# yard-ice-power.net
KiCad netlist of a schematic drawn in Altium Designer
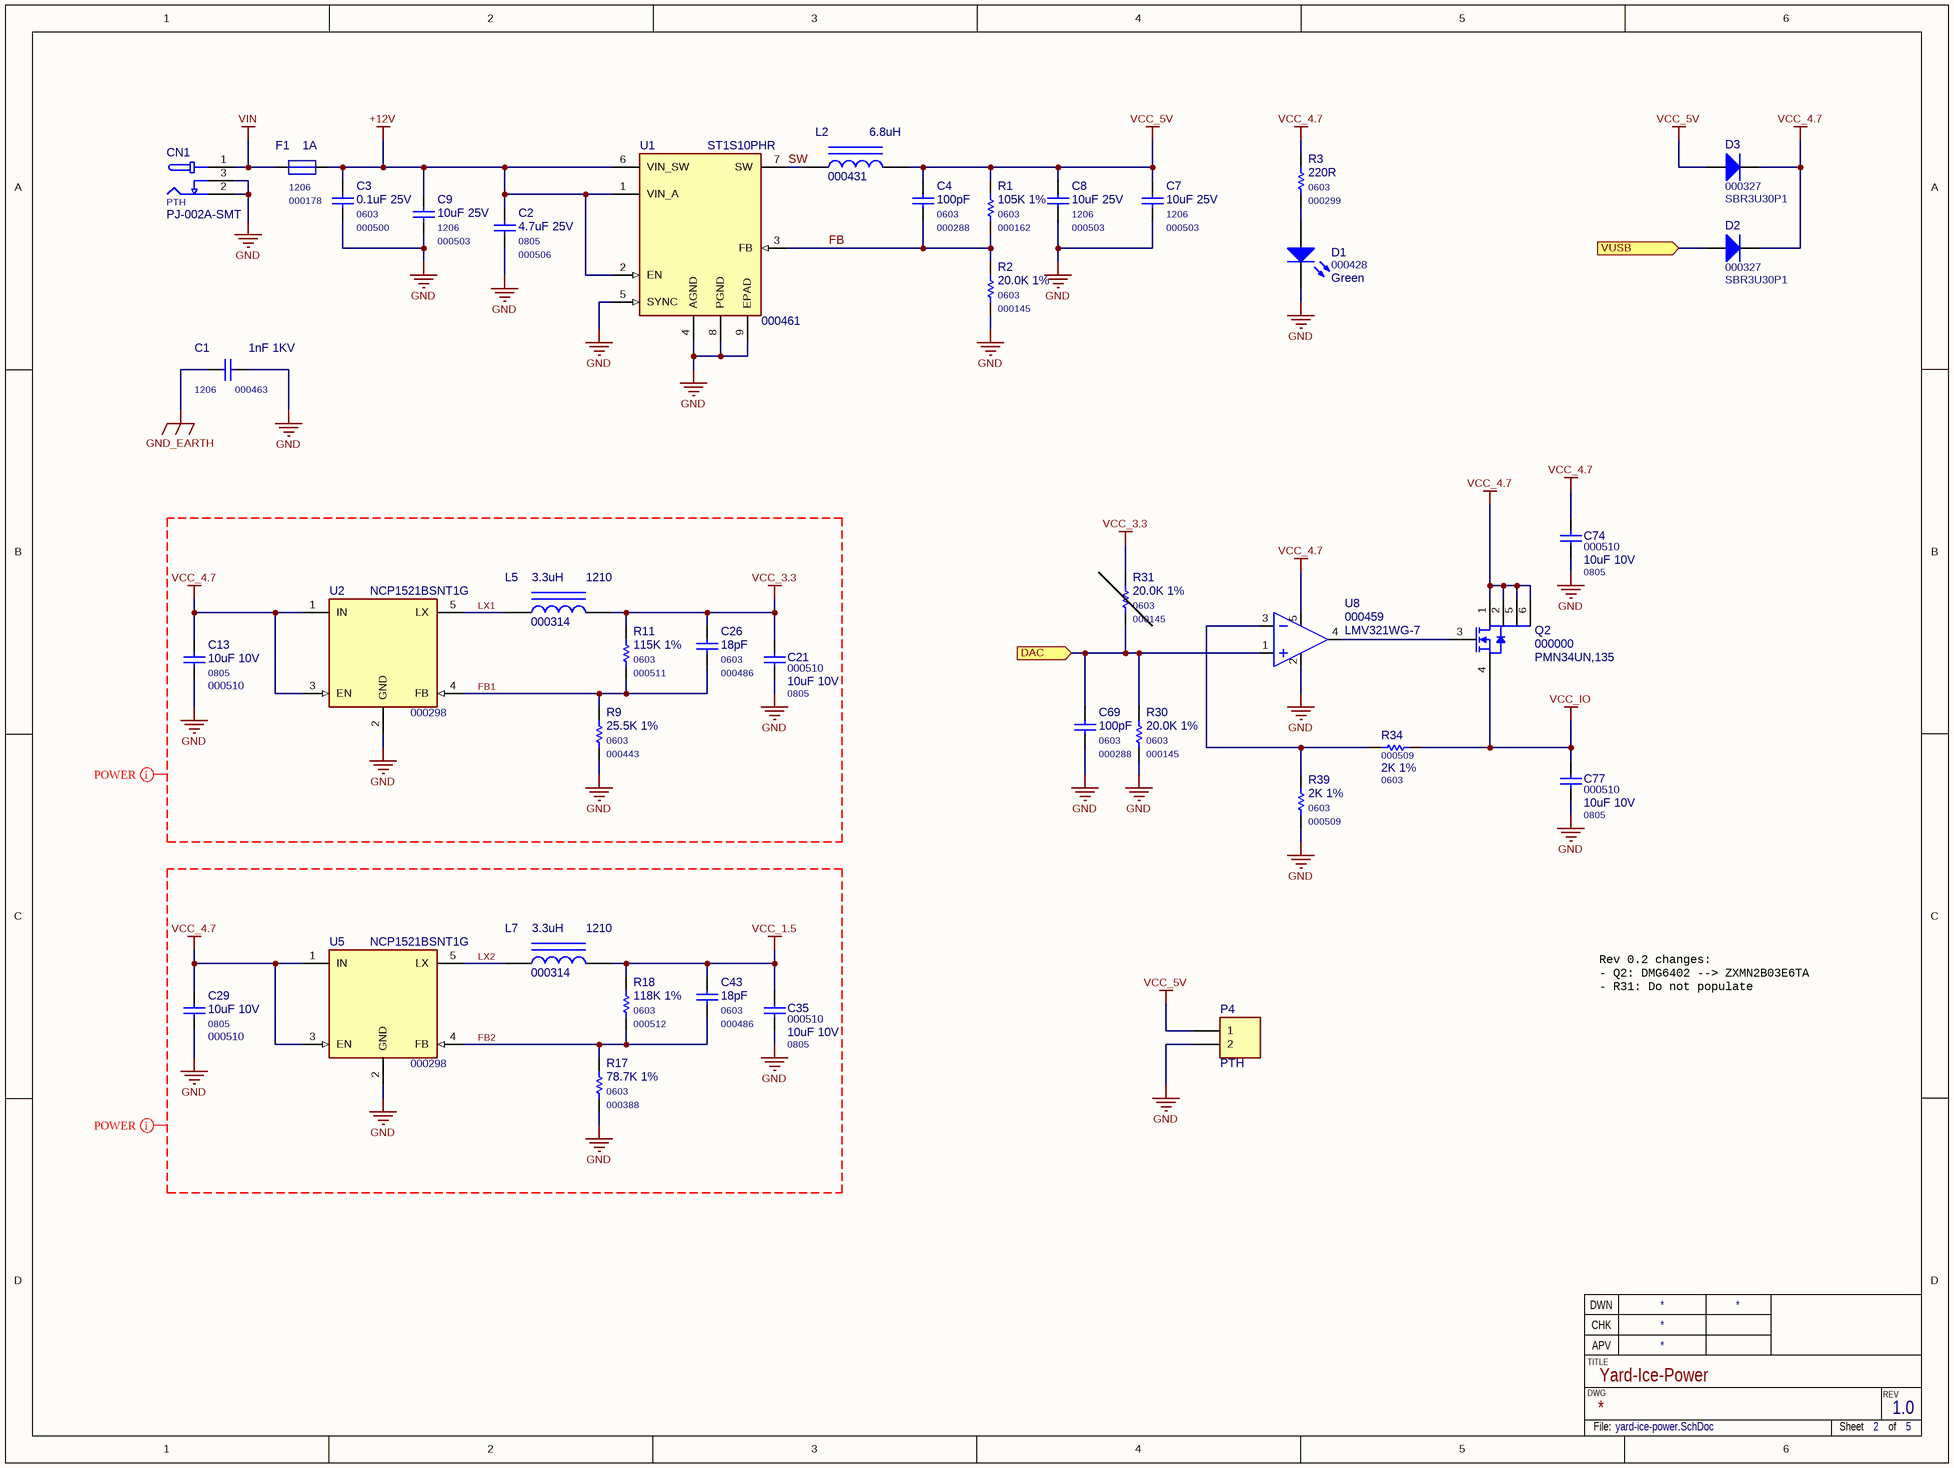
[diagram p0: yard-ice-power.SchDoc]

(export (version "E")
  (design (tool "Eeschema 10.0.6"))
  (components
    (comp (ref "C1")
      (value "000463")
      (footprint "C1206M")
      (description "SMD Ceramic Chip Capacitor - 1206")
      (fields (field (name "ALTIUM_VALUE") "1nF 1KV") (field (name "PACKAGE") "1206"))
      (libsource (lib "discrete-sm") (part "C1206"))
    )
    (comp (ref "C2")
      (value "000506")
      (footprint "C0805M")
      (description "SMD Ceramic Chip Capacitor - 0805 - X7R")
      (fields
        (field (name "ALTIUM_VALUE") "4.7uF 25V")
        (field (name "PACKAGE") "0805")
        (field (name "MF") "Taiyo Yuden")
      )
      (libsource (lib "discrete-sm") (part "C0805"))
    )
    (comp (ref "C3")
      (value "000500")
      (footprint "C0603M")
      (description "SMD Ceramic Chip Capacitor - 0603 - X7R")
      (fields
        (field (name "ALTIUM_VALUE") "0.1uF 25V")
        (field (name "PACKAGE") "0603")
        (field (name "MF") "TDK")
      )
      (libsource (lib "discrete-sm") (part "C0603"))
    )
    (comp (ref "C4")
      (value "000288")
      (footprint "C0603M")
      (description "SMD Ceramic Chip Capacitor - 0603")
      (fields (field (name "ALTIUM_VALUE") "100pF") (field (name "PACKAGE") "0603"))
      (libsource (lib "discrete-sm") (part "C0603"))
    )
    (comp (ref "C7")
      (value "000503")
      (footprint "C1206M")
      (description "SMD Ceramic Chip Capacitor - 1206 - X7R")
      (fields
        (field (name "ALTIUM_VALUE") "10uF 25V")
        (field (name "PACKAGE") "1206")
        (field (name "MF") "Taiyo Yuden")
      )
      (libsource (lib "discrete-sm") (part "C1206"))
    )
    (comp (ref "C8")
      (value "000503")
      (footprint "C1206M")
      (description "SMD Ceramic Chip Capacitor - 1206 - X7R")
      (fields
        (field (name "ALTIUM_VALUE") "10uF 25V")
        (field (name "PACKAGE") "1206")
        (field (name "MF") "Taiyo Yuden")
      )
      (libsource (lib "discrete-sm") (part "C1206"))
    )
    (comp (ref "C9")
      (value "000503")
      (footprint "C1206M")
      (description "SMD Ceramic Chip Capacitor - 1206 - X7R")
      (fields
        (field (name "ALTIUM_VALUE") "10uF 25V")
        (field (name "PACKAGE") "1206")
        (field (name "MF") "Taiyo Yuden")
      )
      (libsource (lib "discrete-sm") (part "C1206"))
    )
    (comp (ref "C13")
      (value "000510")
      (footprint "C0805M")
      (description "SMD Ceramic Chip Capacitor - 0805 - X7R")
      (fields
        (field (name "ALTIUM_VALUE") "10uF 10V")
        (field (name "PACKAGE") "0805")
        (field (name "MF") "TDK")
      )
      (libsource (lib "sm_cap") (part "C0805"))
    )
    (comp (ref "C21")
      (value "000510")
      (footprint "C0805M")
      (description "SMD Ceramic Chip Capacitor - 0805 - X7R")
      (fields
        (field (name "ALTIUM_VALUE") "10uF 10V")
        (field (name "PACKAGE") "0805")
        (field (name "MF") "TDK")
      )
      (libsource (lib "sm_cap") (part "C0805"))
    )
    (comp (ref "C26")
      (value "000486")
      (footprint "C0603M")
      (description "SMD Ceramic Chip Capacitor - 0603")
      (fields (field (name "ALTIUM_VALUE") "18pF") (field (name "PACKAGE") "0603"))
      (libsource (lib "discrete-sm") (part "C0603"))
    )
    (comp (ref "C29")
      (value "000510")
      (footprint "C0805M")
      (description "SMD Ceramic Chip Capacitor - 0805 - X7R")
      (fields
        (field (name "ALTIUM_VALUE") "10uF 10V")
        (field (name "PACKAGE") "0805")
        (field (name "MF") "TDK")
      )
      (libsource (lib "sm_cap") (part "C0805"))
    )
    (comp (ref "C35")
      (value "000510")
      (footprint "C0805M")
      (description "SMD Ceramic Chip Capacitor - 0805 - X7R")
      (fields
        (field (name "ALTIUM_VALUE") "10uF 10V")
        (field (name "PACKAGE") "0805")
        (field (name "MF") "TDK")
      )
      (libsource (lib "sm_cap") (part "C0805"))
    )
    (comp (ref "C43")
      (value "000486")
      (footprint "C0603M")
      (description "SMD Ceramic Chip Capacitor - 0603")
      (fields (field (name "ALTIUM_VALUE") "18pF") (field (name "PACKAGE") "0603"))
      (libsource (lib "discrete-sm") (part "C0603"))
    )
    (comp (ref "C69")
      (value "000288")
      (footprint "C0603M")
      (description "SMD Ceramic Chip Capacitor - 0603")
      (fields (field (name "ALTIUM_VALUE") "100pF") (field (name "PACKAGE") "0603"))
      (libsource (lib "discrete-sm") (part "C0603"))
    )
    (comp (ref "C74")
      (value "TDK")
      (footprint "C0805M")
      (description "SMD Ceramic Chip Capacitor - 0805 - X7R")
      (fields (field (name "ALTIUM_VALUE") "10uF 10V") (field (name "PACKAGE") "0805"))
      (libsource (lib "sm_cap") (part "C0805"))
    )
    (comp (ref "C77")
      (value "TDK")
      (footprint "C0805M")
      (description "SMD Ceramic Chip Capacitor - 0805 - X7R")
      (fields (field (name "ALTIUM_VALUE") "10uF 10V") (field (name "PACKAGE") "0805"))
      (libsource (lib "sm_cap") (part "C0805"))
    )
    (comp (ref "CN1")
      (value "PTH")
      (footprint "PJ-002A-SMT")
      (description "Low Voltage Power Supply Connector")
      (fields (field (name "MF") "CUI INC") (field (name "MF PN") "PJ-002A-SMT"))
      (libsource (lib "cui") (part "PJ-002A-SMT"))
    )
    (comp (ref "D1")
      (value "000428")
      (footprint "LED0805L LP")
      (description "LED SMD 0805")
      (fields (field (name "ALTIUM_VALUE") "Green"))
      (libsource (lib "discrete-sm") (part "LED0805LP"))
    )
    (comp (ref "D2")
      (value "000327")
      (footprint "PowerDI 123")
      (description "Super Barrier Rectifier")
      (fields (field (name "ALTIUM_VALUE") "SBR3U30P1") (field (name "MF") "Diodes Inc"))
      (libsource (lib "diodes-inc") (part "SBR3U30P1"))
    )
    (comp (ref "D3")
      (value "000327")
      (footprint "PowerDI 123")
      (description "Super Barrier Rectifier")
      (fields (field (name "ALTIUM_VALUE") "SBR3U30P1") (field (name "MF") "Diodes Inc"))
      (libsource (lib "diodes-inc") (part "SBR3U30P1"))
    )
    (comp (ref "F1")
      (value "000178")
      (footprint "F1206L")
      (description "SMD Fuse, 1A, Slow, 63VDC, 1206")
      (fields
        (field (name "ALTIUM_VALUE") "1A")
        (field (name "PACKAGE") "1206")
        (field (name "MF") "Bel Fuse Inc")
      )
      (libsource (lib "discrete-sm") (part "F1206"))
    )
    (comp (ref "L2")
      (value "000431")
      (footprint "L8.0MMX8.0MM")
      (description "SMT Power Inductor 8.0X8.0mm")
      (fields (field (name "ALTIUM_VALUE") "6.8uH") (field (name "MF") "Taiyo Yuden"))
      (libsource (lib "discrete-sm") (part "L8.0X8.0"))
    )
    (comp (ref "L5")
      (value "000314")
      (footprint "L1210M")
      (description "SMD Wire Wound Inductor -  1210 (3225 metric)")
      (fields
        (field (name "MF") "Murata")
        (field (name "PACKAGE") "1210")
        (field (name "ALTIUM_VALUE") "3.3uH")
      )
      (libsource (lib "discrete-sm") (part "L1210"))
    )
    (comp (ref "L7")
      (value "000314")
      (footprint "L1210M")
      (description "SMD Wire Wound Inductor -  1210 (3225 metric)")
      (fields
        (field (name "MF") "Murata")
        (field (name "PACKAGE") "1210")
        (field (name "ALTIUM_VALUE") "3.3uH")
      )
      (libsource (lib "discrete-sm") (part "L1210"))
    )
    (comp (ref "P4")
      (value "PTH")
      (footprint "TSW-102-07-G-S")
      (description "Header, 2-Pin")
      (libsource (lib "samtec-board-to-board") (part "Header 2"))
    )
    (comp (ref "Q2")
      (value "000000")
      (footprint "SOT-26")
      (description "N-Channel MOSFET 30V 4.9A 6TSOP")
      (fields (field (name "ALTIUM_VALUE") "PMN34UN,135"))
      (libsource (lib "nxp") (part "PMN34UN,135"))
    )
    (comp (ref "R1")
      (value "000162")
      (footprint "R0603M")
      (description "SMD Chip Resistor - 0603")
      (fields (field (name "ALTIUM_VALUE") "105K 1%") (field (name "PACKAGE") "0603"))
      (libsource (lib "discrete-sm") (part "R0603"))
    )
    (comp (ref "R2")
      (value "000145")
      (footprint "R0603M")
      (description "SMD Chip Resistor - 0603")
      (fields (field (name "ALTIUM_VALUE") "20.0K 1%") (field (name "PACKAGE") "0603"))
      (libsource (lib "discrete-sm") (part "R0603"))
    )
    (comp (ref "R3")
      (value "000299")
      (footprint "R0603M")
      (description "SMD Chip Resistor - 0603")
      (fields (field (name "ALTIUM_VALUE") "220R") (field (name "PACKAGE") "0603"))
      (libsource (lib "discrete-sm") (part "R0603"))
    )
    (comp (ref "R9")
      (value "000443")
      (footprint "R0603M")
      (description "SMD Chip Resistor - 0603")
      (fields (field (name "ALTIUM_VALUE") "25.5K 1%") (field (name "PACKAGE") "0603"))
      (libsource (lib "discrete-sm") (part "R0603"))
    )
    (comp (ref "R11")
      (value "000511")
      (footprint "R0603M")
      (description "SMD Chip Resistor - 0603")
      (fields (field (name "ALTIUM_VALUE") "115K 1%") (field (name "PACKAGE") "0603"))
      (libsource (lib "discrete-sm") (part "R0603"))
    )
    (comp (ref "R17")
      (value "000388")
      (footprint "R0603M")
      (description "SMD Chip Resistor - 0603")
      (fields (field (name "ALTIUM_VALUE") "78.7K 1%") (field (name "PACKAGE") "0603"))
      (libsource (lib "discrete-sm") (part "R0603"))
    )
    (comp (ref "R18")
      (value "000512")
      (footprint "R0603M")
      (description "SMD Chip Resistor - 0603")
      (fields (field (name "ALTIUM_VALUE") "118K 1%") (field (name "PACKAGE") "0603"))
      (libsource (lib "discrete-sm") (part "R0603"))
    )
    (comp (ref "R30")
      (value "000145")
      (footprint "R0603M")
      (description "SMD Chip Resistor - 0603")
      (fields (field (name "ALTIUM_VALUE") "20.0K 1%") (field (name "PACKAGE") "0603"))
      (libsource (lib "discrete-sm") (part "R0603"))
    )
    (comp (ref "R31")
      (value "000145")
      (footprint "R0603M")
      (description "SMD Chip Resistor - 0603")
      (fields (field (name "ALTIUM_VALUE") "20.0K 1%") (field (name "PACKAGE") "0603"))
      (libsource (lib "discrete-sm") (part "R0603"))
    )
    (comp (ref "R34")
      (value "000509")
      (footprint "R0603M")
      (description "SMD Chip Resistor - 0603")
      (fields (field (name "ALTIUM_VALUE") "2K 1%") (field (name "PACKAGE") "0603"))
      (libsource (lib "discrete-sm") (part "R0603"))
    )
    (comp (ref "R39")
      (value "000509")
      (footprint "R0603M")
      (description "SMD Chip Resistor - 0603")
      (fields (field (name "ALTIUM_VALUE") "2K 1%") (field (name "PACKAGE") "0603"))
      (libsource (lib "discrete-sm") (part "R0603"))
    )
    (comp (ref "U1")
      (value "000461")
      (footprint "PowerSO-8")
      (description "3A, 900kHZ, monolithic synchronous step-down regulator")
      (fields (field (name "ALTIUM_VALUE") "ST1S10PHR") (field (name "MF") "ST"))
      (libsource (lib "st-pwr-mgmt") (part "ST1S10"))
    )
    (comp (ref "U2")
      (value "000298")
      (footprint "TSOP-5")
      (description "1.5 MHz, 600 mA Step-Down  DC-DC Converter")
      (fields (field (name "MF") "ON Semiconductor") (field (name "ALTIUM_VALUE") "NCP1521BSNT1G"))
      (libsource (lib "on-semi") (part "NCP1521BSNT1G"))
    )
    (comp (ref "U5")
      (value "000298")
      (footprint "TSOP-5")
      (description "1.5 MHz, 600 mA Step-Down  DC-DC Converter")
      (fields (field (name "MF") "ON Semiconductor") (field (name "ALTIUM_VALUE") "NCP1521BSNT1G"))
      (libsource (lib "on-semi") (part "NCP1521BSNT1G"))
    )
    (comp (ref "U8")
      (value "000459")
      (footprint "SOT-25")
      (description "General Purpose, Low Voltage, Rail-to-Rail Output Operational Amplifier")
      (fields (field (name "ALTIUM_VALUE") "LMV321WG-7") (field (name "MF") "Diodes Inc"))
      (libsource (lib "diodes-inc-opamp") (part "LMV321WG-7"))
    )
  )
  (nets
    (net (code "1") (name "+12V") (class "Default")
      (node (ref "C2") (pin "1") (pinfunction "1_1") (pintype "passive"))
      (node (ref "C3") (pin "1") (pinfunction "1_1") (pintype "passive"))
      (node (ref "C9") (pin "1") (pinfunction "1_1") (pintype "passive"))
      (node (ref "F1") (pin "2") (pinfunction "2_2") (pintype "passive"))
      (node (ref "U1") (pin "1") (pinfunction "VIN_A_1") (pintype "power_in"))
      (node (ref "U1") (pin "2") (pinfunction "EN_2") (pintype "input"))
      (node (ref "U1") (pin "6") (pinfunction "VIN_SW_6") (pintype "power_in"))
    )
    (net (code "2") (name "/DAC") (class "Default")
      (node (ref "C69") (pin "1") (pinfunction "1_1") (pintype "passive"))
      (node (ref "R30") (pin "2") (pinfunction "2_2") (pintype "passive"))
      (node (ref "R31") (pin "1") (pinfunction "1_1") (pintype "passive"))
      (node (ref "U8") (pin "1") (pinfunction "IN+_1") (pintype "passive"))
    )
    (net (code "3") (name "/FB") (class "Default")
      (node (ref "C4") (pin "2") (pinfunction "2_2") (pintype "passive"))
      (node (ref "R1") (pin "1") (pinfunction "1_1") (pintype "passive"))
      (node (ref "R2") (pin "2") (pinfunction "2_2") (pintype "passive"))
      (node (ref "U1") (pin "3") (pinfunction "FB_3") (pintype "input"))
    )
    (net (code "4") (name "/FB1") (class "Default")
      (node (ref "C26") (pin "2") (pinfunction "2_2") (pintype "passive"))
      (node (ref "R11") (pin "1") (pinfunction "1_1") (pintype "passive"))
      (node (ref "R9") (pin "2") (pinfunction "2_2") (pintype "passive"))
      (node (ref "U2") (pin "4") (pinfunction "FB_4") (pintype "input"))
    )
    (net (code "5") (name "/FB2") (class "Default")
      (node (ref "C43") (pin "2") (pinfunction "2_2") (pintype "passive"))
      (node (ref "R17") (pin "2") (pinfunction "2_2") (pintype "passive"))
      (node (ref "R18") (pin "1") (pinfunction "1_1") (pintype "passive"))
      (node (ref "U5") (pin "4") (pinfunction "FB_4") (pintype "input"))
    )
    (net (code "6") (name "/LX1") (class "Default")
      (node (ref "L5") (pin "1") (pinfunction "1_1") (pintype "passive"))
      (node (ref "U2") (pin "5") (pinfunction "LX_5") (pintype "open_collector"))
    )
    (net (code "7") (name "/LX2") (class "Default")
      (node (ref "L7") (pin "1") (pinfunction "1_1") (pintype "passive"))
      (node (ref "U5") (pin "5") (pinfunction "LX_5") (pintype "open_collector"))
    )
    (net (code "8") (name "/SW") (class "Default")
      (node (ref "L2") (pin "1") (pinfunction "1_1") (pintype "passive"))
      (node (ref "U1") (pin "7") (pinfunction "SW_7") (pintype "open_collector"))
    )
    (net (code "9") (name "/VUSB") (class "Default")
      (node (ref "D2") (pin "1") (pinfunction "A_1") (pintype "passive"))
    )
    (net (code "10") (name "GND") (class "Default")
      (node (ref "C1") (pin "2") (pinfunction "2_2") (pintype "passive"))
      (node (ref "C13") (pin "2") (pinfunction "2_2") (pintype "passive"))
      (node (ref "C2") (pin "2") (pinfunction "2_2") (pintype "passive"))
      (node (ref "C21") (pin "2") (pinfunction "2_2") (pintype "passive"))
      (node (ref "C29") (pin "2") (pinfunction "2_2") (pintype "passive"))
      (node (ref "C3") (pin "2") (pinfunction "2_2") (pintype "passive"))
      (node (ref "C35") (pin "2") (pinfunction "2_2") (pintype "passive"))
      (node (ref "C69") (pin "2") (pinfunction "2_2") (pintype "passive"))
      (node (ref "C7") (pin "2") (pinfunction "2_2") (pintype "passive"))
      (node (ref "C74") (pin "2") (pinfunction "2_2") (pintype "passive"))
      (node (ref "C77") (pin "2") (pinfunction "2_2") (pintype "passive"))
      (node (ref "C8") (pin "2") (pinfunction "2_2") (pintype "passive"))
      (node (ref "C9") (pin "2") (pinfunction "2_2") (pintype "passive"))
      (node (ref "CN1") (pin "2") (pinfunction "2_2") (pintype "power_in"))
      (node (ref "CN1") (pin "3") (pinfunction "3_3") (pintype "power_in"))
      (node (ref "D1") (pin "2") (pinfunction "K_2") (pintype "passive"))
      (node (ref "P4") (pin "2") (pinfunction "2_2") (pintype "passive"))
      (node (ref "R17") (pin "1") (pinfunction "1_1") (pintype "passive"))
      (node (ref "R2") (pin "1") (pinfunction "1_1") (pintype "passive"))
      (node (ref "R30") (pin "1") (pinfunction "1_1") (pintype "passive"))
      (node (ref "R39") (pin "1") (pinfunction "1_1") (pintype "passive"))
      (node (ref "R9") (pin "1") (pinfunction "1_1") (pintype "passive"))
      (node (ref "U1") (pin "4") (pinfunction "AGND_4") (pintype "power_in"))
      (node (ref "U1") (pin "5") (pinfunction "SYNC_5") (pintype "input"))
      (node (ref "U1") (pin "8") (pinfunction "PGND_8") (pintype "power_in"))
      (node (ref "U1") (pin "9") (pinfunction "EPAD_9") (pintype "power_in"))
      (node (ref "U2") (pin "2") (pinfunction "GND_2") (pintype "power_in"))
      (node (ref "U5") (pin "2") (pinfunction "GND_2") (pintype "power_in"))
      (node (ref "U8") (pin "2") (pinfunction "V-_2") (pintype "power_in"))
    )
    (net (code "11") (name "GND_EARTH") (class "Default")
      (node (ref "C1") (pin "1") (pinfunction "1_1") (pintype "passive"))
    )
    (net (code "12") (name "Net-(D1-A)") (class "Default")
      (node (ref "D1") (pin "1") (pinfunction "A_1") (pintype "passive"))
      (node (ref "R3") (pin "1") (pinfunction "1_1") (pintype "passive"))
    )
    (net (code "13") (name "Net-(Q2-G)") (class "Default")
      (node (ref "Q2") (pin "3") (pinfunction "G_3") (pintype "passive"))
      (node (ref "U8") (pin "4") (pinfunction "OUT_4") (pintype "passive"))
    )
    (net (code "14") (name "Net-(U8-IN-)") (class "Default")
      (node (ref "R34") (pin "2") (pinfunction "2_2") (pintype "passive"))
      (node (ref "R39") (pin "2") (pinfunction "2_2") (pintype "passive"))
      (node (ref "U8") (pin "3") (pinfunction "IN-_3") (pintype "passive"))
    )
    (net (code "15") (name "VCC_1.5") (class "Default")
      (node (ref "C35") (pin "1") (pinfunction "1_1") (pintype "passive"))
      (node (ref "C43") (pin "1") (pinfunction "1_1") (pintype "passive"))
      (node (ref "L7") (pin "2") (pinfunction "2_2") (pintype "passive"))
      (node (ref "R18") (pin "2") (pinfunction "2_2") (pintype "passive"))
    )
    (net (code "16") (name "VCC_3.3") (class "Default")
      (node (ref "C21") (pin "1") (pinfunction "1_1") (pintype "passive"))
      (node (ref "C26") (pin "1") (pinfunction "1_1") (pintype "passive"))
      (node (ref "L5") (pin "2") (pinfunction "2_2") (pintype "passive"))
      (node (ref "R11") (pin "2") (pinfunction "2_2") (pintype "passive"))
      (node (ref "R31") (pin "2") (pinfunction "2_2") (pintype "passive"))
    )
    (net (code "17") (name "VCC_4.7") (class "Default")
      (node (ref "C13") (pin "1") (pinfunction "1_1") (pintype "passive"))
      (node (ref "C29") (pin "1") (pinfunction "1_1") (pintype "passive"))
      (node (ref "C74") (pin "1") (pinfunction "1_1") (pintype "passive"))
      (node (ref "D2") (pin "2") (pinfunction "K_2") (pintype "passive"))
      (node (ref "D3") (pin "2") (pinfunction "K_2") (pintype "passive"))
      (node (ref "Q2") (pin "1") (pinfunction "D_1") (pintype "passive"))
      (node (ref "Q2") (pin "2") (pinfunction "D_2") (pintype "passive"))
      (node (ref "Q2") (pin "5") (pinfunction "D_5") (pintype "passive"))
      (node (ref "Q2") (pin "6") (pinfunction "D_6") (pintype "passive"))
      (node (ref "R3") (pin "2") (pinfunction "2_2") (pintype "passive"))
      (node (ref "U2") (pin "1") (pinfunction "IN_1") (pintype "power_in"))
      (node (ref "U2") (pin "3") (pinfunction "EN_3") (pintype "input"))
      (node (ref "U5") (pin "1") (pinfunction "IN_1") (pintype "power_in"))
      (node (ref "U5") (pin "3") (pinfunction "EN_3") (pintype "input"))
      (node (ref "U8") (pin "5") (pinfunction "V+_5") (pintype "power_in"))
    )
    (net (code "18") (name "VCC_5V") (class "Default")
      (node (ref "C4") (pin "1") (pinfunction "1_1") (pintype "passive"))
      (node (ref "C7") (pin "1") (pinfunction "1_1") (pintype "passive"))
      (node (ref "C8") (pin "1") (pinfunction "1_1") (pintype "passive"))
      (node (ref "D3") (pin "1") (pinfunction "A_1") (pintype "passive"))
      (node (ref "L2") (pin "2") (pinfunction "2_2") (pintype "passive"))
      (node (ref "P4") (pin "1") (pinfunction "1_1") (pintype "passive"))
      (node (ref "R1") (pin "2") (pinfunction "2_2") (pintype "passive"))
    )
    (net (code "19") (name "VCC_IO") (class "Default")
      (node (ref "C77") (pin "1") (pinfunction "1_1") (pintype "passive"))
      (node (ref "Q2") (pin "4") (pinfunction "S_4") (pintype "passive"))
      (node (ref "R34") (pin "1") (pinfunction "1_1") (pintype "passive"))
    )
    (net (code "20") (name "VIN") (class "Default")
      (node (ref "CN1") (pin "1") (pinfunction "1_1") (pintype "power_in"))
      (node (ref "F1") (pin "1") (pinfunction "1_1") (pintype "passive"))
    )
  )
)
